# lora1280m.net
KiCad netlist of a schematic drawn in Altium Designer
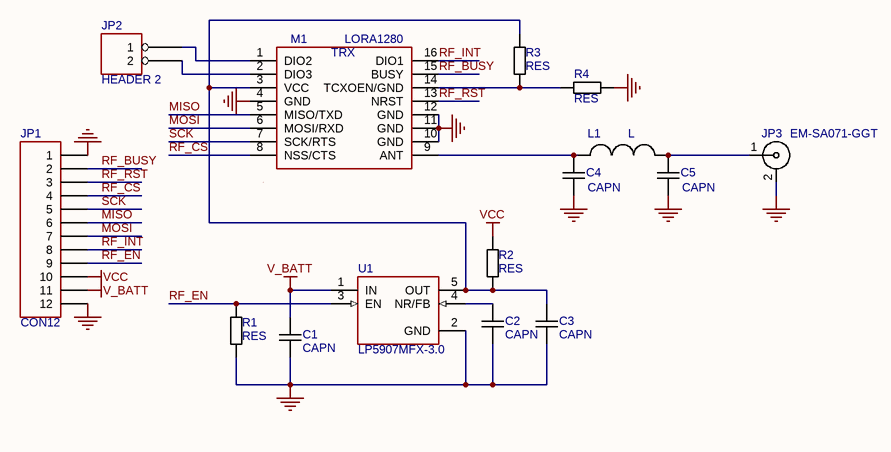
[diagram p0: lora1280m.SchDoc]

(export (version "E")
  (design (tool "Eeschema 10.0.6"))
  (components
    (comp (ref "C1")
      (value "CAPN")
      (footprint "C-0805")
      (fields (field (name "VOLTAGE") "50V"))
      (libsource (lib "Passive") (part "CAPN"))
    )
    (comp (ref "C2")
      (value "CAPN")
      (footprint "C-0603")
      (fields (field (name "VOLTAGE") "50V"))
      (libsource (lib "Passive") (part "CAPN"))
    )
    (comp (ref "C3")
      (value "CAPN")
      (footprint "C-0805")
      (fields (field (name "VOLTAGE") "50V"))
      (libsource (lib "Passive") (part "CAPN"))
    )
    (comp (ref "C4")
      (value "CAPN")
      (footprint "C-0603")
      (fields (field (name "VOLTAGE") "50V"))
      (libsource (lib "Passive") (part "CAPN"))
    )
    (comp (ref "C5")
      (value "CAPN")
      (footprint "C-0603")
      (fields (field (name "VOLTAGE") "50V"))
      (libsource (lib "Passive") (part "CAPN"))
    )
    (comp (ref "JP1")
      (value "CON12")
      (footprint "PBS1-12R")
      (description "Connector")
      (libsource (lib "Connectors") (part "CON12"))
    )
    (comp (ref "JP2")
      (value "HEADER 2")
      (footprint "PLS1-2")
      (libsource (lib "Connectors") (part "HEADER 2"))
    )
    (comp (ref "JP3")
      (value "EM-SA071-GGT")
      (footprint "SMA_F_EDGE")
      (description "SMA Female R/A PCB Mount")
      (libsource (lib "Connectors") (part "SMA"))
    )
    (comp (ref "L1") (value "L") (footprint "L-0603") (libsource (lib "Passive") (part "L")))
    (comp (ref "M1")
      (value "LORA1280")
      (footprint "LGA16_LORA1280")
      (libsource (lib "RFmodules") (part "LORA1280"))
    )
    (comp (ref "R1") (value "RES") (footprint "R-0603") (libsource (lib "Passive") (part "RES")))
    (comp (ref "R2") (value "RES") (footprint "R-0603") (libsource (lib "Passive") (part "RES")))
    (comp (ref "R3") (value "RES") (footprint "R-0603") (libsource (lib "") (part "RES_2")))
    (comp (ref "R4") (value "RES") (footprint "R-0603") (libsource (lib "") (part "RES_1")))
    (comp (ref "U1")
      (value "LP5907MFX-3.0")
      (footprint "SOT-23-5")
      (description "250mA Low-Dropout Regulator")
      (libsource (lib "ICs") (part "LP5907"))
    )
  )
  (nets
    (net (code "1") (name "/MISO") (class "Default")
      (node (ref "JP1") (pin "6") (pinfunction "6_6") (pintype "passive"))
      (node (ref "M1") (pin "5") (pinfunction "MISO/TXD_5") (pintype "passive"))
    )
    (net (code "2") (name "/MOSI") (class "Default")
      (node (ref "JP1") (pin "7") (pinfunction "7_7") (pintype "passive"))
      (node (ref "M1") (pin "6") (pinfunction "MOSI/RXD_6") (pintype "passive"))
    )
    (net (code "3") (name "/RF_BUSY") (class "Default")
      (node (ref "JP1") (pin "2") (pinfunction "2_2") (pintype "passive"))
      (node (ref "M1") (pin "15") (pinfunction "BUSY_15") (pintype "passive"))
    )
    (net (code "4") (name "/RF_CS") (class "Default")
      (node (ref "JP1") (pin "4") (pinfunction "4_4") (pintype "passive"))
      (node (ref "M1") (pin "8") (pinfunction "NSS/CTS_8") (pintype "passive"))
    )
    (net (code "5") (name "/RF_EN") (class "Default")
      (node (ref "JP1") (pin "9") (pinfunction "9_9") (pintype "passive"))
      (node (ref "R1") (pin "2") (pinfunction "2_2") (pintype "passive"))
      (node (ref "U1") (pin "3") (pinfunction "EN_3") (pintype "input"))
    )
    (net (code "6") (name "/RF_INT") (class "Default")
      (node (ref "JP1") (pin "8") (pinfunction "8_8") (pintype "passive"))
      (node (ref "M1") (pin "16") (pinfunction "DIO1_16") (pintype "passive"))
    )
    (net (code "7") (name "/RF_RST") (class "Default")
      (node (ref "JP1") (pin "3") (pinfunction "3_3") (pintype "passive"))
      (node (ref "M1") (pin "13") (pinfunction "NRST_13") (pintype "passive"))
    )
    (net (code "8") (name "/SCK") (class "Default")
      (node (ref "JP1") (pin "5") (pinfunction "5_5") (pintype "passive"))
      (node (ref "M1") (pin "7") (pinfunction "SCK/RTS_7") (pintype "passive"))
    )
    (net (code "9") (name "GND") (class "Default")
      (node (ref "C1") (pin "2") (pinfunction "2_2") (pintype "passive"))
      (node (ref "C2") (pin "2") (pinfunction "2_2") (pintype "passive"))
      (node (ref "C3") (pin "2") (pinfunction "2_2") (pintype "passive"))
      (node (ref "C4") (pin "2") (pinfunction "2_2") (pintype "passive"))
      (node (ref "C5") (pin "2") (pinfunction "2_2") (pintype "passive"))
      (node (ref "JP1") (pin "1") (pinfunction "1_1") (pintype "passive"))
      (node (ref "JP1") (pin "12") (pinfunction "12_12") (pintype "passive"))
      (node (ref "JP3") (pin "2") (pinfunction "2_2") (pintype "passive"))
      (node (ref "M1") (pin "10") (pinfunction "GND_10") (pintype "passive"))
      (node (ref "M1") (pin "11") (pinfunction "GND_11") (pintype "passive"))
      (node (ref "M1") (pin "12") (pinfunction "GND_12") (pintype "passive"))
      (node (ref "M1") (pin "4") (pinfunction "GND_4") (pintype "passive"))
      (node (ref "R1") (pin "1") (pinfunction "1_1") (pintype "passive"))
      (node (ref "R4") (pin "1") (pinfunction "1_1") (pintype "passive"))
      (node (ref "U1") (pin "2") (pinfunction "GND_2") (pintype "power_in"))
    )
    (net (code "10") (name "Net-(C5-Pad1)") (class "Default")
      (node (ref "C5") (pin "1") (pinfunction "1_1") (pintype "passive"))
      (node (ref "JP3") (pin "1") (pinfunction "1_1") (pintype "passive"))
      (node (ref "L1") (pin "2") (pinfunction "2_2") (pintype "passive"))
    )
    (net (code "11") (name "Net-(M1-ANT)") (class "Default")
      (node (ref "C4") (pin "1") (pinfunction "1_1") (pintype "passive"))
      (node (ref "L1") (pin "1") (pinfunction "1_1") (pintype "passive"))
      (node (ref "M1") (pin "9") (pinfunction "ANT_9") (pintype "passive"))
    )
    (net (code "12") (name "Net-(M1-DIO2)") (class "Default")
      (node (ref "JP2") (pin "1") (pinfunction "1_1") (pintype "passive"))
      (node (ref "M1") (pin "1") (pinfunction "DIO2_1") (pintype "passive"))
    )
    (net (code "13") (name "Net-(M1-DIO3)") (class "Default")
      (node (ref "JP2") (pin "2") (pinfunction "2_2") (pintype "passive"))
      (node (ref "M1") (pin "2") (pinfunction "DIO3_2") (pintype "passive"))
    )
    (net (code "14") (name "Net-(M1-TCXOEN{slash}GND)") (class "Default")
      (node (ref "M1") (pin "14") (pinfunction "TCXOEN/GND_14") (pintype "passive"))
      (node (ref "R3") (pin "2") (pinfunction "2_2") (pintype "passive"))
      (node (ref "R4") (pin "2") (pinfunction "2_2") (pintype "passive"))
    )
    (net (code "15") (name "Net-(M1-VCC)") (class "Default")
      (node (ref "C3") (pin "1") (pinfunction "1_1") (pintype "passive"))
      (node (ref "M1") (pin "3") (pinfunction "VCC_3") (pintype "passive"))
      (node (ref "R2") (pin "1") (pinfunction "1_1") (pintype "passive"))
      (node (ref "R3") (pin "1") (pinfunction "1_1") (pintype "passive"))
      (node (ref "U1") (pin "5") (pinfunction "OUT_5") (pintype "power_in"))
    )
    (net (code "16") (name "Net-(U1-NR{slash}FB)") (class "Default")
      (node (ref "C2") (pin "1") (pinfunction "1_1") (pintype "passive"))
      (node (ref "U1") (pin "4") (pinfunction "NR/FB_4") (pintype "input"))
    )
    (net (code "17") (name "VCC") (class "Default")
      (node (ref "JP1") (pin "10") (pinfunction "10_10") (pintype "passive"))
      (node (ref "R2") (pin "2") (pinfunction "2_2") (pintype "passive"))
    )
    (net (code "18") (name "V_BATT") (class "Default")
      (node (ref "C1") (pin "1") (pinfunction "1_1") (pintype "passive"))
      (node (ref "JP1") (pin "11") (pinfunction "11_11") (pintype "passive"))
      (node (ref "U1") (pin "1") (pinfunction "IN_1") (pintype "power_in"))
    )
  )
)
